# skull.net
KiCad netlist of a schematic drawn in EAGLE
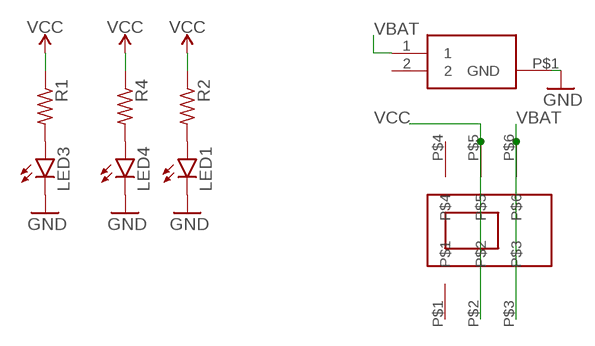
[diagram p0: schematic, sheet 1]

(export (version "E")
  (design (tool "Eeschema 10.0.6"))
  (components
    (comp (ref "LED1")
      (value "LEDCHIP-LED0805")
      (footprint "eagle-import:CHIP-LED0805")
      (libsource (lib "eagle-import") (part "LEDCHIP-LED0805"))
    )
    (comp (ref "LED3")
      (value "LEDCHIP-LED0805")
      (footprint "eagle-import:CHIP-LED0805")
      (libsource (lib "eagle-import") (part "LEDCHIP-LED0805"))
    )
    (comp (ref "LED4")
      (value "LEDCHIP-LED0805")
      (footprint "eagle-import:CHIP-LED0805")
      (libsource (lib "eagle-import") (part "LEDCHIP-LED0805"))
    )
    (comp (ref "R1")
      (value "R-US_R0603")
      (footprint "eagle-import:R0603")
      (libsource (lib "eagle-import") (part "R-US_R0603"))
    )
    (comp (ref "R2")
      (value "R-US_R0603")
      (footprint "eagle-import:R0603")
      (libsource (lib "eagle-import") (part "R-US_R0603"))
    )
    (comp (ref "R4")
      (value "R-US_R0603")
      (footprint "eagle-import:R0603")
      (libsource (lib "eagle-import") (part "R-US_R0603"))
    )
    (comp (ref "U$1")
      (value "CL-SB-22A-02T-SLIDE-SWITCH-TUCKED-PADS")
      (footprint "eagle-import:CL-SB-22A-02T-DPDT-COMPACT-SWITCH")
      (libsource (lib "eagle-import") (part "CL-SB-22A-02T-SLIDE-SWITCH-TUCKED-PADS"))
    )
    (comp (ref "VBAT")
      (value "BAT-HLD-012-SMT")
      (footprint "eagle-import:BATHLD012SMT")
      (fields (field (name "MOUSER_PART_NUMBER") "712-BAT-HLD-012-SMT"))
      (libsource (lib "eagle-import") (part "BAT-HLD-012-SMT"))
    )
  )
  (nets
    (net (code "1") (name "/VBAT") (class "Default")
      (node (ref "U$1") (pin "P$3") (pinfunction "P$3_P$3") (pintype "bidirectional"))
      (node (ref "U$1") (pin "P$6") (pinfunction "P$6_P$6") (pintype "bidirectional"))
      (node (ref "VBAT") (pin "1") (pinfunction "1_1") (pintype "bidirectional"))
    )
    (net (code "2") (name "GND") (class "Default")
      (node (ref "LED1") (pin "C") (pinfunction "C_C") (pintype "passive"))
      (node (ref "LED3") (pin "C") (pinfunction "C_C") (pintype "passive"))
      (node (ref "LED4") (pin "C") (pinfunction "C_C") (pintype "passive"))
      (node (ref "VBAT") (pin "P$1") (pinfunction "GND_P$1") (pintype "bidirectional"))
    )
    (net (code "3") (name "Net-(LED1-PadA)") (class "Default")
      (node (ref "LED1") (pin "A") (pinfunction "A_A") (pintype "passive"))
      (node (ref "R2") (pin "2") (pinfunction "2_2") (pintype "passive"))
    )
    (net (code "4") (name "Net-(LED3-PadA)") (class "Default")
      (node (ref "LED3") (pin "A") (pinfunction "A_A") (pintype "passive"))
      (node (ref "R1") (pin "2") (pinfunction "2_2") (pintype "passive"))
    )
    (net (code "5") (name "Net-(LED4-PadA)") (class "Default")
      (node (ref "LED4") (pin "A") (pinfunction "A_A") (pintype "passive"))
      (node (ref "R4") (pin "2") (pinfunction "2_2") (pintype "passive"))
    )
    (net (code "6") (name "VCC") (class "Default")
      (node (ref "R1") (pin "1") (pinfunction "1_1") (pintype "passive"))
      (node (ref "R2") (pin "1") (pinfunction "1_1") (pintype "passive"))
      (node (ref "R4") (pin "1") (pinfunction "1_1") (pintype "passive"))
      (node (ref "U$1") (pin "P$2") (pinfunction "P$2_P$2") (pintype "bidirectional"))
      (node (ref "U$1") (pin "P$5") (pinfunction "P$5_P$5") (pintype "bidirectional"))
    )
    (net (code "7") (name "unconnected-(U$1-PadP$1)") (class "Default")
      (node (ref "U$1") (pin "P$1") (pinfunction "P$1_P$1") (pintype "bidirectional"))
    )
    (net (code "8") (name "unconnected-(U$1-PadP$4)") (class "Default")
      (node (ref "U$1") (pin "P$4") (pinfunction "P$4_P$4") (pintype "bidirectional"))
    )
    (net (code "9") (name "unconnected-(VBAT-Pad2)") (class "Default")
      (node (ref "VBAT") (pin "2") (pinfunction "2_2") (pintype "bidirectional"))
    )
  )
)
